# Shield_bmp280_Lora.net
KiCad netlist of a schematic drawn in EAGLE
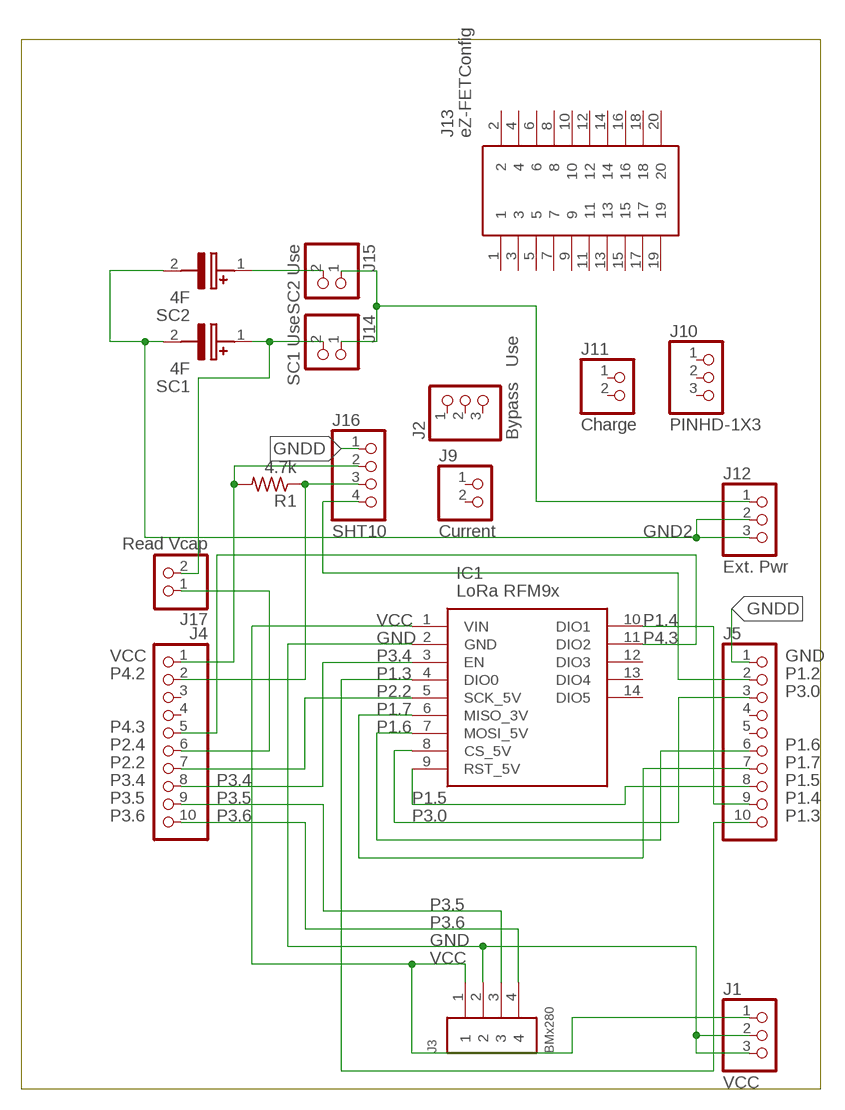
[diagram p0: schematic, sheet 1]

(export (version "E")
  (design (tool "Eeschema 10.0.6"))
  (components
    (comp (ref "IC1")
      (value "LoRa RFM9x")
      (footprint "eagle-import:3072")
      (fields (field (name "MANUFACTURER_PART_NUMBER") "3072") (field (name "MOUSER_PART_NUMBER") "485-3072"))
      (libsource (lib "eagle-import") (part "3072"))
    )
    (comp (ref "J1")
      (value "VCC")
      (footprint "eagle-import:1X03")
      (libsource (lib "eagle-import") (part "PINHD-1X3"))
    )
    (comp (ref "J2")
      (value "Bypass Use")
      (footprint "eagle-import:1X03")
      (libsource (lib "eagle-import") (part "PINHD-1X3"))
    )
    (comp (ref "J3")
      (value "BMx280")
      (footprint "eagle-import:61300411121")
      (fields
        (field (name "DIGI_KEY_PART_NUMBER") "732-5317-ND")
        (field (name "MANUFACTURER") "Wurth Electronics Inc.")
        (field (name "MPN") "61300411121")
        (field (name "CREATED_BY") "PCBLayout.com")
      )
      (libsource (lib "eagle-import") (part "61300411121"))
    )
    (comp (ref "J4")
      (value "VCC")
      (footprint "eagle-import:1X10-BIG")
      (libsource (lib "eagle-import") (part "PINHD-1X10"))
    )
    (comp (ref "J5")
      (value "GND")
      (footprint "eagle-import:1X10-BIG")
      (libsource (lib "eagle-import") (part "PINHD-1X10"))
    )
    (comp (ref "J9")
      (value "Current")
      (footprint "eagle-import:1X02")
      (libsource (lib "eagle-import") (part "PINHD-1X2"))
    )
    (comp (ref "J10")
      (value "PINHD-1X3")
      (footprint "eagle-import:1X03")
      (libsource (lib "eagle-import") (part "PINHD-1X3"))
    )
    (comp (ref "J11")
      (value "Charge")
      (footprint "eagle-import:1X02")
      (libsource (lib "eagle-import") (part "PINHD-1X2"))
    )
    (comp (ref "J12")
      (value "Ext. Pwr")
      (footprint "eagle-import:1X03")
      (libsource (lib "eagle-import") (part "PINHD-1X3"))
    )
    (comp (ref "J13")
      (value "eZ-FETConfig")
      (footprint "eagle-import:HWS1881")
      (fields (field (name "MANUFACTURER_PART_NUMBER") "HWS1881"))
      (libsource (lib "eagle-import") (part "HWS1881"))
    )
    (comp (ref "J14")
      (value "SC1 Use")
      (footprint "eagle-import:1X02")
      (libsource (lib "eagle-import") (part "PINHD-1X2"))
    )
    (comp (ref "J15")
      (value "SC2 Use")
      (footprint "eagle-import:1X02")
      (libsource (lib "eagle-import") (part "PINHD-1X2"))
    )
    (comp (ref "J16")
      (value "SHT10")
      (footprint "eagle-import:1X04")
      (libsource (lib "eagle-import") (part "PINHD-1X4"))
    )
    (comp (ref "J17")
      (value "Read Vcap")
      (footprint "eagle-import:1X02")
      (libsource (lib "eagle-import") (part "PINHD-1X2"))
    )
    (comp (ref "R1")
      (value "4.7k")
      (footprint "eagle-import:0204_7")
      (libsource (lib "eagle-import") (part "R-US_0204/7"))
    )
    (comp (ref "SC1")
      (value "4F")
      (footprint "eagle-import:EECRG0V105VN")
      (fields
        (field (name "MANUFACTURER_PART_NUMBER") "EEC-RG0V105VN")
        (field (name "MOUSER_PART_NUMBER") "667-EEC-RG0V105VN")
      )
      (libsource (lib "eagle-import") (part "EEC-RG0V105VN"))
    )
    (comp (ref "SC2")
      (value "4F")
      (footprint "eagle-import:EECRG0V105VN")
      (fields
        (field (name "MANUFACTURER_PART_NUMBER") "EEC-RG0V105VN")
        (field (name "MOUSER_PART_NUMBER") "667-EEC-RG0V105VN")
      )
      (libsource (lib "eagle-import") (part "EEC-RG0V105VN"))
    )
  )
  (nets
    (net (code "1") (name "/GND") (class "Default")
      (node (ref "IC1") (pin "2") (pinfunction "GND_2") (pintype "bidirectional"))
      (node (ref "J1") (pin "2") (pinfunction "2_2") (pintype "passive"))
      (node (ref "J1") (pin "3") (pinfunction "3_3") (pintype "passive"))
      (node (ref "J3") (pin "2") (pinfunction "2_2") (pintype "passive"))
    )
    (net (code "2") (name "/GND2") (class "Default")
      (node (ref "J12") (pin "2") (pinfunction "2_2") (pintype "passive"))
      (node (ref "J12") (pin "3") (pinfunction "3_3") (pintype "passive"))
      (node (ref "SC1") (pin "2") (pinfunction "-_2") (pintype "bidirectional"))
      (node (ref "SC2") (pin "2") (pinfunction "-_2") (pintype "bidirectional"))
    )
    (net (code "3") (name "/P1.2") (class "Default")
      (node (ref "J16") (pin "4") (pinfunction "4_4") (pintype "passive"))
      (node (ref "J5") (pin "2") (pinfunction "2_2") (pintype "passive"))
    )
    (net (code "4") (name "/P1.3") (class "Default")
      (node (ref "IC1") (pin "4") (pinfunction "DIO0_4") (pintype "bidirectional"))
      (node (ref "J5") (pin "10") (pinfunction "10_10") (pintype "passive"))
    )
    (net (code "5") (name "/P1.4") (class "Default")
      (node (ref "IC1") (pin "10") (pinfunction "DIO1_10") (pintype "bidirectional"))
      (node (ref "J5") (pin "9") (pinfunction "9_9") (pintype "passive"))
    )
    (net (code "6") (name "/P1.5") (class "Default")
      (node (ref "IC1") (pin "9") (pinfunction "RST_5V_9") (pintype "bidirectional"))
      (node (ref "J5") (pin "8") (pinfunction "8_8") (pintype "passive"))
    )
    (net (code "7") (name "/P1.6") (class "Default")
      (node (ref "IC1") (pin "7") (pinfunction "MOSI_5V_7") (pintype "bidirectional"))
      (node (ref "J5") (pin "6") (pinfunction "6_6") (pintype "passive"))
    )
    (net (code "8") (name "/P1.7") (class "Default")
      (node (ref "IC1") (pin "6") (pinfunction "MISO_3V_6") (pintype "bidirectional"))
      (node (ref "J5") (pin "7") (pinfunction "7_7") (pintype "passive"))
    )
    (net (code "9") (name "/P2.2") (class "Default")
      (node (ref "IC1") (pin "5") (pinfunction "SCK_5V_5") (pintype "bidirectional"))
      (node (ref "J4") (pin "7") (pinfunction "7_7") (pintype "passive"))
    )
    (net (code "10") (name "/P2.4") (class "Default")
      (node (ref "J17") (pin "1") (pinfunction "1_1") (pintype "passive"))
      (node (ref "J4") (pin "6") (pinfunction "6_6") (pintype "passive"))
    )
    (net (code "11") (name "/P3.0") (class "Default")
      (node (ref "IC1") (pin "8") (pinfunction "CS_5V_8") (pintype "bidirectional"))
      (node (ref "J5") (pin "3") (pinfunction "3_3") (pintype "passive"))
    )
    (net (code "12") (name "/P3.4") (class "Default")
      (node (ref "IC1") (pin "3") (pinfunction "EN_3") (pintype "bidirectional"))
      (node (ref "J4") (pin "8") (pinfunction "8_8") (pintype "passive"))
    )
    (net (code "13") (name "/P3.5") (class "Default")
      (node (ref "J3") (pin "3") (pinfunction "3_3") (pintype "passive"))
      (node (ref "J4") (pin "9") (pinfunction "9_9") (pintype "passive"))
    )
    (net (code "14") (name "/P3.6") (class "Default")
      (node (ref "J3") (pin "4") (pinfunction "4_4") (pintype "passive"))
      (node (ref "J4") (pin "10") (pinfunction "10_10") (pintype "passive"))
    )
    (net (code "15") (name "/P4.2") (class "Default")
      (node (ref "J16") (pin "3") (pinfunction "3_3") (pintype "passive"))
      (node (ref "J4") (pin "2") (pinfunction "2_2") (pintype "passive"))
      (node (ref "R1") (pin "1") (pinfunction "1_1") (pintype "passive"))
    )
    (net (code "16") (name "/P4.3") (class "Default")
      (node (ref "IC1") (pin "11") (pinfunction "DIO2_11") (pintype "bidirectional"))
      (node (ref "J4") (pin "5") (pinfunction "5_5") (pintype "passive"))
    )
    (net (code "17") (name "/VCC") (class "Default")
      (node (ref "IC1") (pin "1") (pinfunction "VIN_1") (pintype "bidirectional"))
      (node (ref "J1") (pin "1") (pinfunction "1_1") (pintype "passive"))
      (node (ref "J3") (pin "1") (pinfunction "1_1") (pintype "passive"))
    )
    (net (code "18") (name "GNDD") (class "Default")
      (node (ref "J16") (pin "1") (pinfunction "1_1") (pintype "passive"))
      (node (ref "J5") (pin "1") (pinfunction "1_1") (pintype "passive"))
    )
    (net (code "19") (name "Net-(J12-Pad1)") (class "Default")
      (node (ref "J12") (pin "1") (pinfunction "1_1") (pintype "passive"))
      (node (ref "J14") (pin "1") (pinfunction "1_1") (pintype "passive"))
      (node (ref "J15") (pin "1") (pinfunction "1_1") (pintype "passive"))
    )
    (net (code "20") (name "Net-(J16-Pad2)") (class "Default")
      (node (ref "J16") (pin "2") (pinfunction "2_2") (pintype "passive"))
      (node (ref "J4") (pin "1") (pinfunction "1_1") (pintype "passive"))
      (node (ref "R1") (pin "2") (pinfunction "2_2") (pintype "passive"))
    )
    (net (code "21") (name "Net-(SC1-+)") (class "Default")
      (node (ref "J14") (pin "2") (pinfunction "2_2") (pintype "passive"))
      (node (ref "J17") (pin "2") (pinfunction "2_2") (pintype "passive"))
      (node (ref "SC1") (pin "1") (pinfunction "+_1") (pintype "bidirectional"))
    )
    (net (code "22") (name "Net-(SC2-+)") (class "Default")
      (node (ref "J15") (pin "2") (pinfunction "2_2") (pintype "passive"))
      (node (ref "SC2") (pin "1") (pinfunction "+_1") (pintype "bidirectional"))
    )
    (net (code "23") (name "unconnected-(IC1-DIO3-Pad12)") (class "Default")
      (node (ref "IC1") (pin "12") (pinfunction "DIO3_12") (pintype "bidirectional"))
    )
    (net (code "24") (name "unconnected-(IC1-DIO4-Pad13)") (class "Default")
      (node (ref "IC1") (pin "13") (pinfunction "DIO4_13") (pintype "bidirectional"))
    )
    (net (code "25") (name "unconnected-(IC1-DIO5-Pad14)") (class "Default")
      (node (ref "IC1") (pin "14") (pinfunction "DIO5_14") (pintype "bidirectional"))
    )
    (net (code "26") (name "unconnected-(J2-Pad1)") (class "Default")
      (node (ref "J2") (pin "1") (pinfunction "1_1") (pintype "passive"))
    )
    (net (code "27") (name "unconnected-(J2-Pad2)") (class "Default")
      (node (ref "J2") (pin "2") (pinfunction "2_2") (pintype "passive"))
    )
    (net (code "28") (name "unconnected-(J2-Pad3)") (class "Default")
      (node (ref "J2") (pin "3") (pinfunction "3_3") (pintype "passive"))
    )
    (net (code "29") (name "unconnected-(J4-Pad3)") (class "Default")
      (node (ref "J4") (pin "3") (pinfunction "3_3") (pintype "passive"))
    )
    (net (code "30") (name "unconnected-(J4-Pad4)") (class "Default")
      (node (ref "J4") (pin "4") (pinfunction "4_4") (pintype "passive"))
    )
    (net (code "31") (name "unconnected-(J5-Pad4)") (class "Default")
      (node (ref "J5") (pin "4") (pinfunction "4_4") (pintype "passive"))
    )
    (net (code "32") (name "unconnected-(J5-Pad5)") (class "Default")
      (node (ref "J5") (pin "5") (pinfunction "5_5") (pintype "passive"))
    )
    (net (code "33") (name "unconnected-(J9-Pad1)") (class "Default")
      (node (ref "J9") (pin "1") (pinfunction "1_1") (pintype "passive"))
    )
    (net (code "34") (name "unconnected-(J9-Pad2)") (class "Default")
      (node (ref "J9") (pin "2") (pinfunction "2_2") (pintype "passive"))
    )
    (net (code "35") (name "unconnected-(J10-Pad1)") (class "Default")
      (node (ref "J10") (pin "1") (pinfunction "1_1") (pintype "passive"))
    )
    (net (code "36") (name "unconnected-(J10-Pad2)") (class "Default")
      (node (ref "J10") (pin "2") (pinfunction "2_2") (pintype "passive"))
    )
    (net (code "37") (name "unconnected-(J10-Pad3)") (class "Default")
      (node (ref "J10") (pin "3") (pinfunction "3_3") (pintype "passive"))
    )
    (net (code "38") (name "unconnected-(J11-Pad1)") (class "Default")
      (node (ref "J11") (pin "1") (pinfunction "1_1") (pintype "passive"))
    )
    (net (code "39") (name "unconnected-(J11-Pad2)") (class "Default")
      (node (ref "J11") (pin "2") (pinfunction "2_2") (pintype "passive"))
    )
    (net (code "40") (name "unconnected-(J13-Pad1)") (class "Default")
      (node (ref "J13") (pin "1") (pinfunction "1_1") (pintype "bidirectional"))
    )
    (net (code "41") (name "unconnected-(J13-Pad2)") (class "Default")
      (node (ref "J13") (pin "2") (pinfunction "2_2") (pintype "bidirectional"))
    )
    (net (code "42") (name "unconnected-(J13-Pad3)") (class "Default")
      (node (ref "J13") (pin "3") (pinfunction "3_3") (pintype "bidirectional"))
    )
    (net (code "43") (name "unconnected-(J13-Pad4)") (class "Default")
      (node (ref "J13") (pin "4") (pinfunction "4_4") (pintype "bidirectional"))
    )
    (net (code "44") (name "unconnected-(J13-Pad5)") (class "Default")
      (node (ref "J13") (pin "5") (pinfunction "5_5") (pintype "bidirectional"))
    )
    (net (code "45") (name "unconnected-(J13-Pad6)") (class "Default")
      (node (ref "J13") (pin "6") (pinfunction "6_6") (pintype "bidirectional"))
    )
    (net (code "46") (name "unconnected-(J13-Pad7)") (class "Default")
      (node (ref "J13") (pin "7") (pinfunction "7_7") (pintype "bidirectional"))
    )
    (net (code "47") (name "unconnected-(J13-Pad8)") (class "Default")
      (node (ref "J13") (pin "8") (pinfunction "8_8") (pintype "bidirectional"))
    )
    (net (code "48") (name "unconnected-(J13-Pad9)") (class "Default")
      (node (ref "J13") (pin "9") (pinfunction "9_9") (pintype "bidirectional"))
    )
    (net (code "49") (name "unconnected-(J13-Pad10)") (class "Default")
      (node (ref "J13") (pin "10") (pinfunction "10_10") (pintype "bidirectional"))
    )
    (net (code "50") (name "unconnected-(J13-Pad11)") (class "Default")
      (node (ref "J13") (pin "11") (pinfunction "11_11") (pintype "bidirectional"))
    )
    (net (code "51") (name "unconnected-(J13-Pad12)") (class "Default")
      (node (ref "J13") (pin "12") (pinfunction "12_12") (pintype "bidirectional"))
    )
    (net (code "52") (name "unconnected-(J13-Pad13)") (class "Default")
      (node (ref "J13") (pin "13") (pinfunction "13_13") (pintype "bidirectional"))
    )
    (net (code "53") (name "unconnected-(J13-Pad14)") (class "Default")
      (node (ref "J13") (pin "14") (pinfunction "14_14") (pintype "bidirectional"))
    )
    (net (code "54") (name "unconnected-(J13-Pad15)") (class "Default")
      (node (ref "J13") (pin "15") (pinfunction "15_15") (pintype "bidirectional"))
    )
    (net (code "55") (name "unconnected-(J13-Pad16)") (class "Default")
      (node (ref "J13") (pin "16") (pinfunction "16_16") (pintype "bidirectional"))
    )
    (net (code "56") (name "unconnected-(J13-Pad17)") (class "Default")
      (node (ref "J13") (pin "17") (pinfunction "17_17") (pintype "bidirectional"))
    )
    (net (code "57") (name "unconnected-(J13-Pad18)") (class "Default")
      (node (ref "J13") (pin "18") (pinfunction "18_18") (pintype "bidirectional"))
    )
    (net (code "58") (name "unconnected-(J13-Pad19)") (class "Default")
      (node (ref "J13") (pin "19") (pinfunction "19_19") (pintype "bidirectional"))
    )
    (net (code "59") (name "unconnected-(J13-Pad20)") (class "Default")
      (node (ref "J13") (pin "20") (pinfunction "20_20") (pintype "bidirectional"))
    )
  )
)
